# voeding.net
KiCad netlist of a schematic drawn in Altium Designer
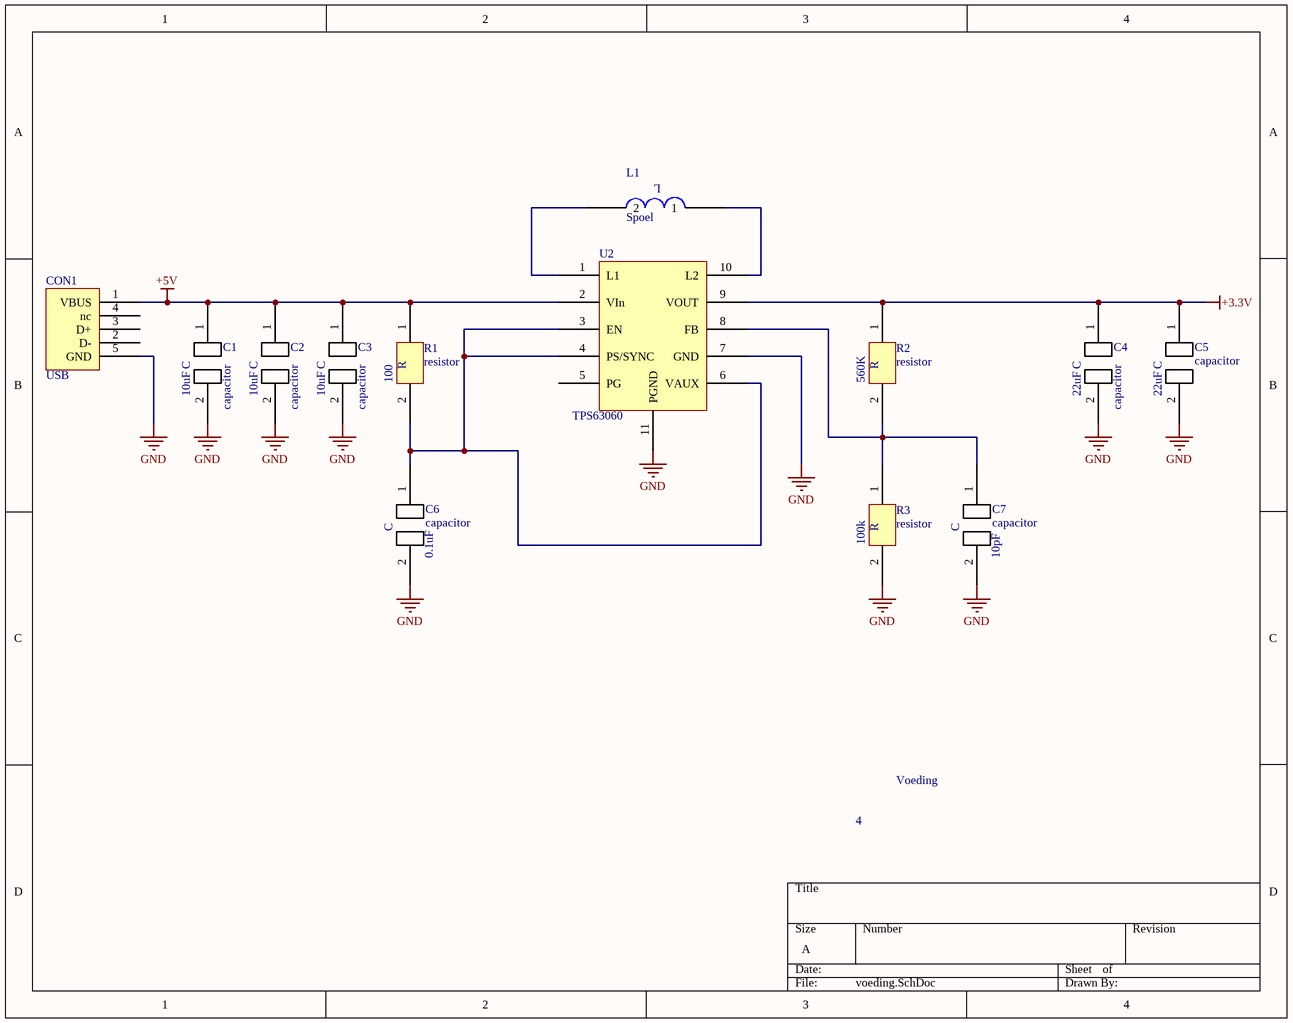
[diagram p0: voeding.SchDoc]

(export (version "E")
  (design (tool "Eeschema 10.0.6"))
  (components
    (comp (ref "C1")
      (value "capacitor")
      (footprint "0603")
      (fields (field (name "ALTIUM_VALUE") "10uF"))
      (libsource (lib "pasives") (part "capacitor"))
    )
    (comp (ref "C2")
      (value "capacitor")
      (footprint "0603")
      (fields (field (name "ALTIUM_VALUE") "10uF"))
      (libsource (lib "pasives") (part "capacitor"))
    )
    (comp (ref "C3")
      (value "capacitor")
      (footprint "0603")
      (fields (field (name "ALTIUM_VALUE") "10uF"))
      (libsource (lib "pasives") (part "capacitor"))
    )
    (comp (ref "C4")
      (value "capacitor")
      (footprint "0603")
      (fields (field (name "ALTIUM_VALUE") "22uF"))
      (libsource (lib "pasives") (part "capacitor"))
    )
    (comp (ref "C5")
      (value "capacitor")
      (footprint "0603")
      (fields (field (name "ALTIUM_VALUE") "22uF"))
      (libsource (lib "pasives") (part "capacitor"))
    )
    (comp (ref "C6")
      (value "capacitor")
      (footprint "0805")
      (fields (field (name "ALTIUM_UNNAMED_1") "0.1uF"))
      (libsource (lib "pasives") (part "capacitor"))
    )
    (comp (ref "C7")
      (value "capacitor")
      (footprint "0805")
      (fields (field (name "ALTIUM_UNNAMED_1") "10pF"))
      (libsource (lib "pasives") (part "capacitor"))
    )
    (comp (ref "CON1") (value "USB") (footprint "USB") (libsource (lib "conector's_and_TP") (part "USB")))
    (comp (ref "L1")
      (value "Spoel")
      (footprint "Coilcraft , XFL4020-102")
      (libsource (lib "pasives") (part "Spoel"))
    )
    (comp (ref "R1")
      (value "resistor")
      (footprint "0603")
      (fields (field (name "ALTIUM_VALUE") "100"))
      (libsource (lib "pasives") (part "resistor"))
    )
    (comp (ref "R2")
      (value "resistor")
      (footprint "0603")
      (fields (field (name "ALTIUM_VALUE") "560K"))
      (libsource (lib "pasives") (part "resistor"))
    )
    (comp (ref "R3")
      (value "resistor")
      (footprint "0603")
      (fields (field (name "ALTIUM_VALUE") "100k"))
      (libsource (lib "pasives") (part "resistor"))
    )
    (comp (ref "U2")
      (value "TPS63060")
      (footprint "TPS63060")
      (libsource (lib "halfgelijders") (part "TPS63060"))
    )
  )
  (nets
    (net (code "1") (name "+3.3V") (class "Default")
      (node (ref "C4") (pin "1") (pinfunction "1_1") (pintype "passive"))
      (node (ref "C5") (pin "1") (pinfunction "1_1") (pintype "passive"))
      (node (ref "R2") (pin "1") (pinfunction "1_1") (pintype "passive"))
      (node (ref "U2") (pin "9") (pinfunction "VOUT_9") (pintype "passive"))
    )
    (net (code "2") (name "+5V") (class "Default")
      (node (ref "C1") (pin "1") (pinfunction "1_1") (pintype "passive"))
      (node (ref "C2") (pin "1") (pinfunction "1_1") (pintype "passive"))
      (node (ref "C3") (pin "1") (pinfunction "1_1") (pintype "passive"))
      (node (ref "CON1") (pin "1") (pinfunction "VBUS_1") (pintype "passive"))
      (node (ref "R1") (pin "1") (pinfunction "1_1") (pintype "passive"))
      (node (ref "U2") (pin "2") (pinfunction "VIn_2") (pintype "passive"))
    )
    (net (code "3") (name "GND") (class "Default")
      (node (ref "C1") (pin "2") (pinfunction "2_2") (pintype "passive"))
      (node (ref "C2") (pin "2") (pinfunction "2_2") (pintype "passive"))
      (node (ref "C3") (pin "2") (pinfunction "2_2") (pintype "passive"))
      (node (ref "C4") (pin "2") (pinfunction "2_2") (pintype "passive"))
      (node (ref "C5") (pin "2") (pinfunction "2_2") (pintype "passive"))
      (node (ref "C6") (pin "2") (pinfunction "2_2") (pintype "passive"))
      (node (ref "C7") (pin "2") (pinfunction "2_2") (pintype "passive"))
      (node (ref "CON1") (pin "5") (pinfunction "GND_5") (pintype "passive"))
      (node (ref "R3") (pin "2") (pinfunction "2_2") (pintype "passive"))
      (node (ref "U2") (pin "11") (pinfunction "PGND_11") (pintype "passive"))
      (node (ref "U2") (pin "7") (pinfunction "GND_7") (pintype "passive"))
    )
    (net (code "4") (name "Net-(U2-EN)") (class "Default")
      (node (ref "C6") (pin "1") (pinfunction "1_1") (pintype "passive"))
      (node (ref "R1") (pin "2") (pinfunction "2_2") (pintype "passive"))
      (node (ref "U2") (pin "3") (pinfunction "EN_3") (pintype "passive"))
      (node (ref "U2") (pin "4") (pinfunction "PS/SYNC_4") (pintype "passive"))
      (node (ref "U2") (pin "6") (pinfunction "VAUX_6") (pintype "passive"))
    )
    (net (code "5") (name "Net-(U2-FB)") (class "Default")
      (node (ref "C7") (pin "1") (pinfunction "1_1") (pintype "passive"))
      (node (ref "R2") (pin "2") (pinfunction "2_2") (pintype "passive"))
      (node (ref "R3") (pin "1") (pinfunction "1_1") (pintype "passive"))
      (node (ref "U2") (pin "8") (pinfunction "FB_8") (pintype "passive"))
    )
    (net (code "6") (name "Net-(U2-L1)") (class "Default")
      (node (ref "L1") (pin "2") (pinfunction "2_2") (pintype "passive"))
      (node (ref "U2") (pin "1") (pinfunction "L1_1") (pintype "passive"))
    )
    (net (code "7") (name "Net-(U2-L2)") (class "Default")
      (node (ref "L1") (pin "1") (pinfunction "1_1") (pintype "passive"))
      (node (ref "U2") (pin "10") (pinfunction "L2_10") (pintype "passive"))
    )
    (net (code "8") (name "unconnected-(CON1-D+-Pad3)") (class "Default")
      (node (ref "CON1") (pin "3") (pinfunction "D+_3") (pintype "passive"))
    )
    (net (code "9") (name "unconnected-(CON1-D--Pad2)") (class "Default")
      (node (ref "CON1") (pin "2") (pinfunction "D-_2") (pintype "passive"))
    )
    (net (code "10") (name "unconnected-(CON1-nc-Pad4)") (class "Default")
      (node (ref "CON1") (pin "4") (pinfunction "nc_4") (pintype "passive"))
    )
    (net (code "11") (name "unconnected-(U2-PG-Pad5)") (class "Default")
      (node (ref "U2") (pin "5") (pinfunction "PG_5") (pintype "passive"))
    )
  )
)
